# SWD_resistor_hack.net
KiCad netlist of a schematic drawn in Altium Designer
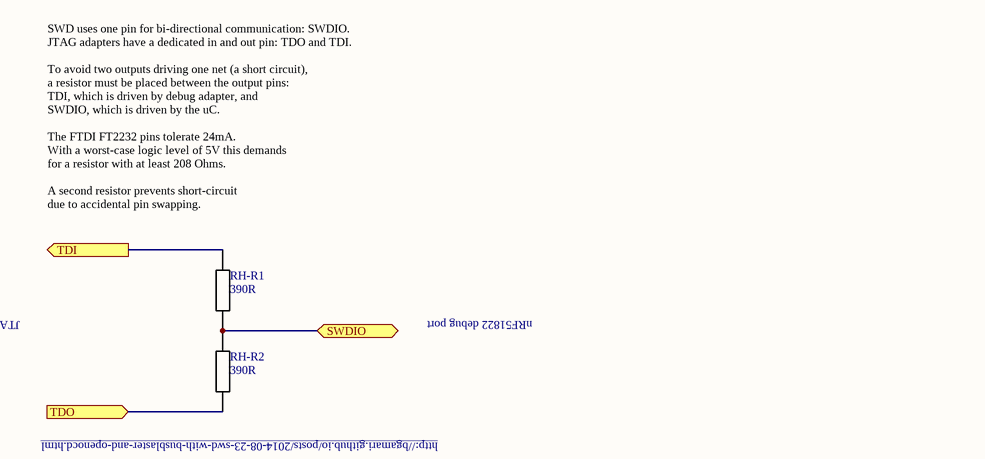
[diagram p0: SWD resistor hack.SchDoc]

(export (version "E")
  (design (tool "Eeschema 10.0.6"))
  (components
    (comp (ref "RH-R1")
      (value "390R")
      (footprint "R 0805 / 2012 wide")
      (libsource (lib "Core51822-related") (part "Resistor"))
    )
    (comp (ref "RH-R2")
      (value "390R")
      (footprint "R 0805 / 2012 wide")
      (libsource (lib "Core51822-related") (part "Resistor"))
    )
  )
  (nets
    (net (code "1") (name "/SWDIO") (class "Default")
      (node (ref "RH-R1") (pin "1") (pinfunction "1_1") (pintype "passive"))
      (node (ref "RH-R2") (pin "2") (pinfunction "2_2") (pintype "passive"))
    )
    (net (code "2") (name "/TDI") (class "Default")
      (node (ref "RH-R1") (pin "2") (pinfunction "2_2") (pintype "passive"))
    )
    (net (code "3") (name "/TDO") (class "Default")
      (node (ref "RH-R2") (pin "1") (pinfunction "1_1") (pintype "passive"))
    )
  )
)
